# XC7A35TFTG256_bank0.net
KiCad netlist of a schematic drawn in Altium Designer
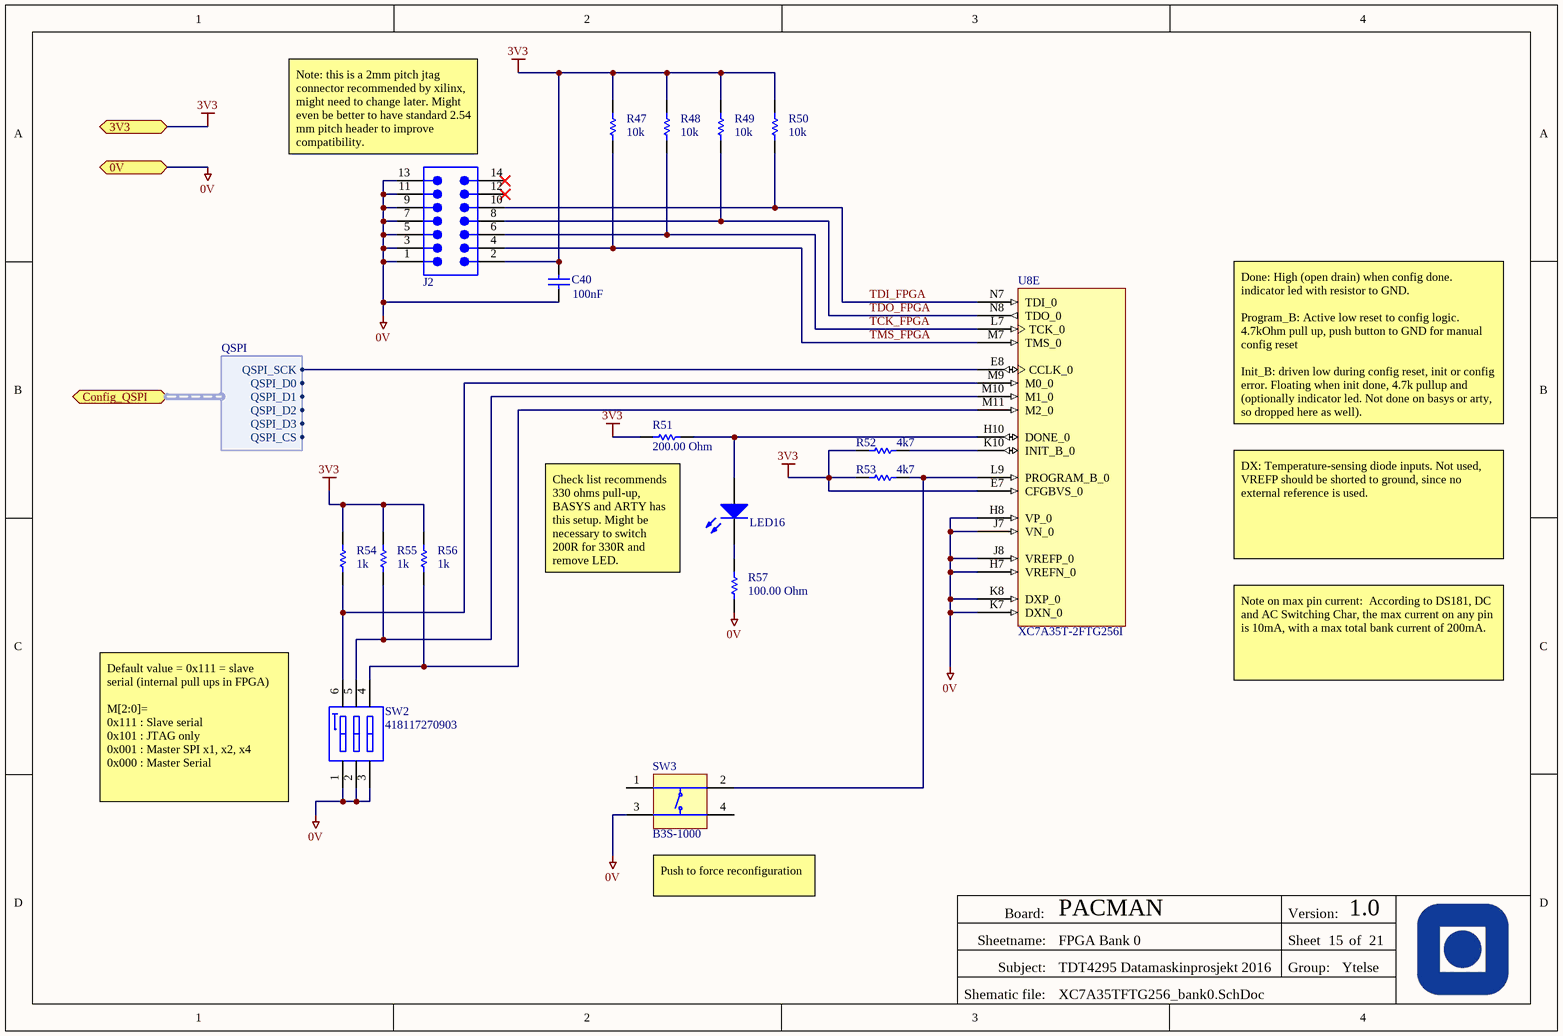
[diagram p0: XC7A35TFTG256_bank0.SchDoc]

(export (version "E")
  (design (tool "Eeschema 10.0.6"))
  (components
    (comp (ref "C40")
      (value "100nF")
      (footprint "CAPC0603(1608)100_M")
      (description "CAP 100nF 16V ±5% 0603 (1608 Metric) Thickness 1mm SMD")
      (fields (field (name "TOLERANCE") "Â±5%") (field (name "Comment") "CAP 100nF 16V 0603(1608)"))
      (libsource (lib "Altium Content Vault") (part "CMP-1035-02583-1"))
    )
    (comp (ref "J2")
      (value "2x7 2mm header")
      (footprint "2x7 2mm")
      (description "2 x 7 2mm pitch vertical header")
      (libsource (lib "dmpro16lib") (part "2x7 2mm header"))
    )
    (comp (ref "LED16")
      (value "150060RS75000")
      (footprint "0603_A")
      (description "SMD mono-color Chip LED, WL-SMCW, Red")
      (fields (field (name "MANUFACTURER") "Wuerth Elektronik"))
      (libsource (lib "Altium Content Vault") (part "CMP-1426-00001-1"))
    )
    (comp (ref "R47")
      (value "10k")
      (footprint "RESC0603(1608)_N")
      (description "10K 0.1W 5% 0603 (1608 Metric)  SMD")
      (fields (field (name "TOLERANCE") "5 %") (field (name "POWER") "0.1 W"))
      (libsource (lib "Altium Content Vault") (part "CMP-1012-00098-1"))
    )
    (comp (ref "R48")
      (value "10k")
      (footprint "RESC0603(1608)_N")
      (description "10K 0.1W 5% 0603 (1608 Metric)  SMD")
      (fields (field (name "TOLERANCE") "5 %") (field (name "POWER") "0.1 W"))
      (libsource (lib "Altium Content Vault") (part "CMP-1012-00098-1"))
    )
    (comp (ref "R49")
      (value "10k")
      (footprint "RESC0603(1608)_N")
      (description "10K 0.1W 5% 0603 (1608 Metric)  SMD")
      (fields (field (name "TOLERANCE") "5 %") (field (name "POWER") "0.1 W"))
      (libsource (lib "Altium Content Vault") (part "CMP-1012-00098-1"))
    )
    (comp (ref "R50")
      (value "10k")
      (footprint "RESC0603(1608)_N")
      (description "10K 0.1W 5% 0603 (1608 Metric)  SMD")
      (fields (field (name "TOLERANCE") "5 %") (field (name "POWER") "0.1 W"))
      (libsource (lib "Altium Content Vault") (part "CMP-1012-00098-1"))
    )
    (comp (ref "R51")
      (value "200.00 Ohm")
      (footprint "RESC0603(1608)_L")
      (description "200R 0.1W 5% 0603 (1608 Metric)  SMD")
      (fields (field (name "TOLERANCE") "5 %") (field (name "POWER") "0.1 W"))
      (libsource (lib "Altium Content Vault") (part "CMP-1012-00057-1"))
    )
    (comp (ref "R52")
      (value "4k7")
      (footprint "RESC0603(1608)_N")
      (description "4K7 0.1W 1% 0603 (1608 Metric)  SMD")
      (fields (field (name "POWER") "0.1 W") (field (name "TOLERANCE") "1 %"))
      (libsource (lib "Altium Content Vault") (part "CMP-1012-00586-1"))
    )
    (comp (ref "R53")
      (value "4k7")
      (footprint "RESC0603(1608)_N")
      (description "4K7 0.1W 1% 0603 (1608 Metric)  SMD")
      (fields (field (name "POWER") "0.1 W") (field (name "TOLERANCE") "1 %"))
      (libsource (lib "Altium Content Vault") (part "CMP-1012-00586-1"))
    )
    (comp (ref "R54")
      (value "1k")
      (footprint "RESC0603(1608)_L")
      (description "1K 0.1W 5% 0603 (1608 Metric)  SMD")
      (fields (field (name "TOLERANCE") "5 %") (field (name "POWER") "0.1 W"))
      (libsource (lib "Altium Content Vault") (part "CMP-1012-00074-1"))
    )
    (comp (ref "R55")
      (value "1k")
      (footprint "RESC0603(1608)_L")
      (description "1K 0.1W 5% 0603 (1608 Metric)  SMD")
      (fields (field (name "TOLERANCE") "5 %") (field (name "POWER") "0.1 W"))
      (libsource (lib "Altium Content Vault") (part "CMP-1012-00074-1"))
    )
    (comp (ref "R56")
      (value "1k")
      (footprint "RESC0603(1608)_L")
      (description "1K 0.1W 5% 0603 (1608 Metric)  SMD")
      (fields (field (name "TOLERANCE") "5 %") (field (name "POWER") "0.1 W"))
      (libsource (lib "Altium Content Vault") (part "CMP-1012-00074-1"))
    )
    (comp (ref "R57")
      (value "100.00 Ohm")
      (footprint "RESC0603(1608)_L")
      (description "100R 0.1W 5% 0603 (1608 Metric)  SMD")
      (fields (field (name "TOLERANCE") "5 %") (field (name "POWER") "0.1 W"))
      (libsource (lib "Altium Content Vault") (part "CMP-1012-00050-1"))
    )
    (comp (ref "SW2")
      (value "418117270903")
      (footprint "418117270903")
      (description "WS-DITV 2.54 mm Compact THT Dip Switch with Raised Actuator")
      (fields (field (name "MANUFACTURER") "Wuerth Elektronik"))
      (libsource (lib "Altium Content Vault") (part "WE-DIP-SW-6"))
    )
    (comp (ref "SW3")
      (value "B3S-1000")
      (footprint "OMRON-B3S-1000-4_V")
      (description "Sealed Tactile Switch, SPST-NO, 3 to 24 V, -25 to 70 degC, 4-Pin SMD, RoHS, Bulk")
      (libsource (lib "Altium Content Vault") (part "SW-SPST-4_A"))
    )
    (comp (ref "U8")
      (value "XC7A35T-2FTG256I")
      (footprint "FTG256")
      (description "Artix-7 FPGA, 170 User I/Os, 0 GTP, 256-Ball BGA, Speed Grade 2, Industrial Grade, Pb-Free")
      (fields (field (name "MANUFACTURER") "Xilinx"))
      (libsource (lib "Altium Content Vault") (part "XLNX-XC7A35T-FTG256"))
    )
  )
  (nets
    (net (code "2") (name "/QSPI_SCK") (class "Default")
      (node (ref "U8") (pin "E8") (pinfunction "CCLK_0_E8") (pintype "bidirectional"))
    )
    (net (code "3") (name "/TCK_FPGA") (class "Default")
      (node (ref "J2") (pin "6") (pinfunction "6_6") (pintype "passive"))
      (node (ref "R48") (pin "1") (pinfunction "1_1") (pintype "passive"))
      (node (ref "U8") (pin "L7") (pinfunction "TCK_0_L7") (pintype "input"))
    )
    (net (code "4") (name "/TDI_FPGA") (class "Default")
      (node (ref "J2") (pin "10") (pinfunction "10_10") (pintype "passive"))
      (node (ref "R50") (pin "1") (pinfunction "1_1") (pintype "passive"))
      (node (ref "U8") (pin "N7") (pinfunction "TDI_0_N7") (pintype "input"))
    )
    (net (code "5") (name "/TDO_FPGA") (class "Default")
      (node (ref "J2") (pin "8") (pinfunction "8_8") (pintype "passive"))
      (node (ref "R49") (pin "1") (pinfunction "1_1") (pintype "passive"))
      (node (ref "U8") (pin "N8") (pinfunction "TDO_0_N8") (pintype "output"))
    )
    (net (code "6") (name "/TMS_FPGA") (class "Default")
      (node (ref "J2") (pin "4") (pinfunction "4_4") (pintype "passive"))
      (node (ref "R47") (pin "1") (pinfunction "1_1") (pintype "passive"))
      (node (ref "U8") (pin "M7") (pinfunction "TMS_0_M7") (pintype "input"))
    )
    (net (code "8") (name "0V") (class "Default")
      (node (ref "C40") (pin "1") (pinfunction "1_1") (pintype "passive"))
      (node (ref "J2") (pin "1") (pinfunction "1_1") (pintype "passive"))
      (node (ref "J2") (pin "11") (pinfunction "11_11") (pintype "passive"))
      (node (ref "J2") (pin "13") (pinfunction "13_13") (pintype "passive"))
      (node (ref "J2") (pin "3") (pinfunction "3_3") (pintype "passive"))
      (node (ref "J2") (pin "5") (pinfunction "5_5") (pintype "passive"))
      (node (ref "J2") (pin "7") (pinfunction "7_7") (pintype "passive"))
      (node (ref "J2") (pin "9") (pinfunction "9_9") (pintype "passive"))
      (node (ref "R57") (pin "1") (pinfunction "1_1") (pintype "passive"))
      (node (ref "SW2") (pin "1") (pinfunction "1_1") (pintype "passive"))
      (node (ref "SW2") (pin "2") (pinfunction "2_2") (pintype "passive"))
      (node (ref "SW2") (pin "3") (pinfunction "3_3") (pintype "passive"))
      (node (ref "SW3") (pin "3") (pinfunction "3_3") (pintype "passive"))
      (node (ref "U8") (pin "H7") (pinfunction "VREFN_0_H7") (pintype "input"))
      (node (ref "U8") (pin "H8") (pinfunction "VP_0_H8") (pintype "input"))
      (node (ref "U8") (pin "J7") (pinfunction "VN_0_J7") (pintype "input"))
      (node (ref "U8") (pin "J8") (pinfunction "VREFP_0_J8") (pintype "input"))
      (node (ref "U8") (pin "K7") (pinfunction "DXN_0_K7") (pintype "input"))
      (node (ref "U8") (pin "K8") (pinfunction "DXP_0_K8") (pintype "input"))
    )
    (net (code "9") (name "3V3") (class "Default")
      (node (ref "C40") (pin "2") (pinfunction "2_2") (pintype "passive"))
      (node (ref "J2") (pin "2") (pinfunction "2_2") (pintype "passive"))
      (node (ref "R47") (pin "2") (pinfunction "2_2") (pintype "passive"))
      (node (ref "R48") (pin "2") (pinfunction "2_2") (pintype "passive"))
      (node (ref "R49") (pin "2") (pinfunction "2_2") (pintype "passive"))
      (node (ref "R50") (pin "2") (pinfunction "2_2") (pintype "passive"))
      (node (ref "R51") (pin "1") (pinfunction "1_1") (pintype "passive"))
      (node (ref "R52") (pin "1") (pinfunction "1_1") (pintype "passive"))
      (node (ref "R53") (pin "1") (pinfunction "1_1") (pintype "passive"))
      (node (ref "R54") (pin "2") (pinfunction "2_2") (pintype "passive"))
      (node (ref "R55") (pin "2") (pinfunction "2_2") (pintype "passive"))
      (node (ref "R56") (pin "2") (pinfunction "2_2") (pintype "passive"))
      (node (ref "U8") (pin "E7") (pinfunction "CFGBVS_0_E7") (pintype "input"))
    )
    (net (code "10") (name "Net-(LED16-A)") (class "Default")
      (node (ref "LED16") (pin "2") (pinfunction "A_2") (pintype "passive"))
      (node (ref "R51") (pin "2") (pinfunction "2_2") (pintype "passive"))
      (node (ref "U8") (pin "H10") (pinfunction "DONE_0_H10") (pintype "bidirectional"))
    )
    (net (code "11") (name "Net-(LED16-K)") (class "Default")
      (node (ref "LED16") (pin "1") (pinfunction "K_1") (pintype "passive"))
      (node (ref "R57") (pin "2") (pinfunction "2_2") (pintype "passive"))
    )
    (net (code "12") (name "Net-(U8E-INIT_B_0)") (class "Default")
      (node (ref "R52") (pin "2") (pinfunction "2_2") (pintype "passive"))
      (node (ref "U8") (pin "K10") (pinfunction "INIT_B_0_K10") (pintype "bidirectional"))
    )
    (net (code "13") (name "Net-(U8E-M0_0)") (class "Default")
      (node (ref "R54") (pin "1") (pinfunction "1_1") (pintype "passive"))
      (node (ref "SW2") (pin "6") (pinfunction "6_6") (pintype "passive"))
      (node (ref "U8") (pin "M9") (pinfunction "M0_0_M9") (pintype "input"))
    )
    (net (code "14") (name "Net-(U8E-M1_0)") (class "Default")
      (node (ref "R55") (pin "1") (pinfunction "1_1") (pintype "passive"))
      (node (ref "SW2") (pin "5") (pinfunction "5_5") (pintype "passive"))
      (node (ref "U8") (pin "M10") (pinfunction "M1_0_M10") (pintype "input"))
    )
    (net (code "15") (name "Net-(U8E-M2_0)") (class "Default")
      (node (ref "R56") (pin "1") (pinfunction "1_1") (pintype "passive"))
      (node (ref "SW2") (pin "4") (pinfunction "4_4") (pintype "passive"))
      (node (ref "U8") (pin "M11") (pinfunction "M2_0_M11") (pintype "input"))
    )
    (net (code "16") (name "Net-(U8E-PROGRAM_B_0)") (class "Default")
      (node (ref "R53") (pin "2") (pinfunction "2_2") (pintype "passive"))
      (node (ref "SW3") (pin "2") (pinfunction "2_2") (pintype "passive"))
      (node (ref "U8") (pin "L9") (pinfunction "PROGRAM_B_0_L9") (pintype "input"))
    )
    (net (code "17") (name "unconnected-(J2-Pad12)") (class "Default")
      (node (ref "J2") (pin "12") (pinfunction "12_12") (pintype "passive+no_connect"))
    )
    (net (code "18") (name "unconnected-(J2-Pad14)") (class "Default")
      (node (ref "J2") (pin "14") (pinfunction "14_14") (pintype "passive+no_connect"))
    )
    (net (code "19") (name "unconnected-(SW3-Pad1)") (class "Default")
      (node (ref "SW3") (pin "1") (pinfunction "1_1") (pintype "passive"))
    )
    (net (code "20") (name "unconnected-(SW3-Pad4)") (class "Default")
      (node (ref "SW3") (pin "4") (pinfunction "4_4") (pintype "passive"))
    )
  )
)
